# Driver.net
KiCad netlist of a schematic drawn in Altium Designer
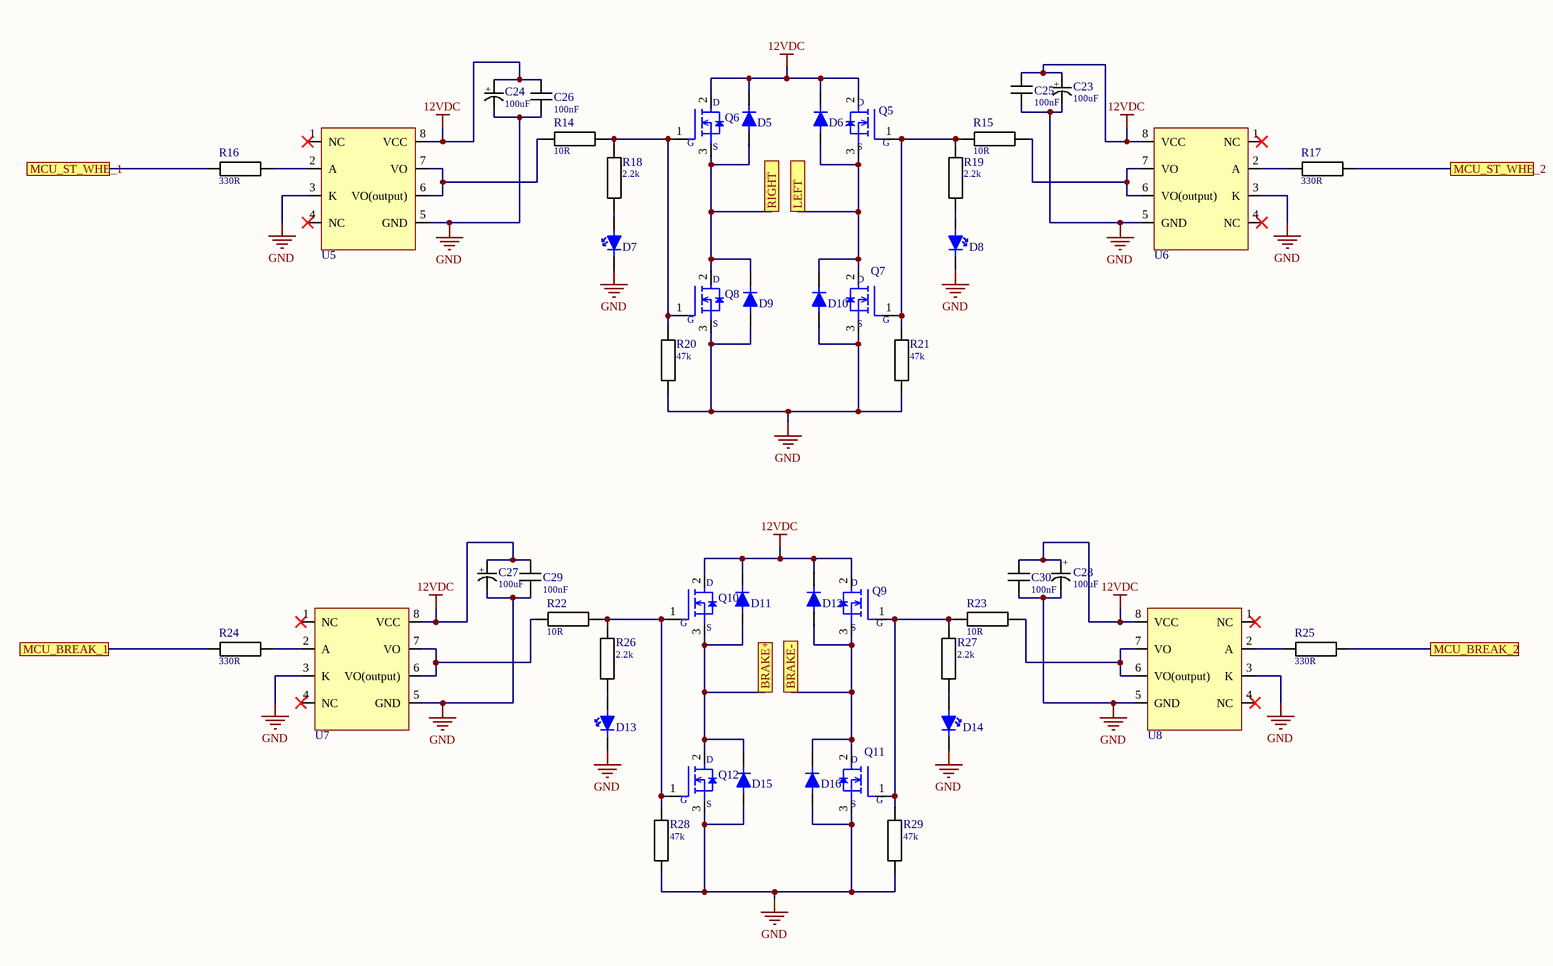
[diagram p0: Driver.SchDoc]

(export (version "E")
  (design (tool "Eeschema 10.0.6"))
  (components
    (comp (ref "C23")
      (value "EEE-HA0J101WR")
      (footprint "CAP_ELEC_EEE-HA0J101WR")
      (description "Cap Aluminum 100uF %20  SMD")
      (fields
        (field (name "MANUFACTURER") "Panasonic")
        (field (name "TOLERANCE") "20%")
        (field (name "CAPACITANCE") "100uF")
        (field (name "DESIGNED BY") "Semih AŞÇI")
      )
      (libsource (lib "Integrated_Library1") (part "CAP 100uF Polar SMD"))
    )
    (comp (ref "C24")
      (value "EEE-HA0J101WR")
      (footprint "CAP_ELEC_EEE-HA0J101WR")
      (description "Cap Aluminum 100uF %20  SMD")
      (fields
        (field (name "MANUFACTURER") "Panasonic")
        (field (name "TOLERANCE") "20%")
        (field (name "CAPACITANCE") "100uF")
        (field (name "DESIGNED BY") "Semih AŞÇI")
      )
      (libsource (lib "Integrated_Library1") (part "CAP 100uF Polar SMD"))
    )
    (comp (ref "C25")
      (value "C0805C104K5RAC7800")
      (footprint "CAP_0805")
      (description "Cap Ceramic 100nF %10 SMD 0805")
      (fields
        (field (name "MANUFACTURER") "KEMET")
        (field (name "MANUFACTURER PART NUMBER") "C0805C104K5RACTU")
        (field (name "CAPACITANCE") "100nF")
        (field (name "DESIGNED BY") "Semih AŞÇI")
      )
      (libsource (lib "Integrated_Library1") (part "CAP 100nF 0805"))
    )
    (comp (ref "C26")
      (value "C0805C104K5RAC7800")
      (footprint "CAP_0805")
      (description "Cap Ceramic 100nF %10 SMD 0805")
      (fields
        (field (name "MANUFACTURER") "KEMET")
        (field (name "MANUFACTURER PART NUMBER") "C0805C104K5RACTU")
        (field (name "CAPACITANCE") "100nF")
        (field (name "DESIGNED BY") "Semih AŞÇI")
      )
      (libsource (lib "Integrated_Library1") (part "CAP 100nF 0805"))
    )
    (comp (ref "C27")
      (value "EEE-HA0J101WR")
      (footprint "CAP_ELEC_EEE-HA0J101WR")
      (description "Cap Aluminum 100uF %20  SMD")
      (fields
        (field (name "MANUFACTURER") "Panasonic")
        (field (name "TOLERANCE") "20%")
        (field (name "CAPACITANCE") "100uF")
        (field (name "DESIGNED BY") "Semih AŞÇI")
      )
      (libsource (lib "Integrated_Library1") (part "CAP 100uF Polar SMD"))
    )
    (comp (ref "C28")
      (value "EEE-HA0J101WR")
      (footprint "CAP_ELEC_EEE-HA0J101WR")
      (description "Cap Aluminum 100uF %20  SMD")
      (fields
        (field (name "MANUFACTURER") "Panasonic")
        (field (name "TOLERANCE") "20%")
        (field (name "CAPACITANCE") "100uF")
        (field (name "DESIGNED BY") "Semih AŞÇI")
      )
      (libsource (lib "") (part "CAP 100uF Polar SMD_1"))
    )
    (comp (ref "C29")
      (value "C0805C104K5RAC7800")
      (footprint "CAP_0805")
      (description "Cap Ceramic 100nF %10 SMD 0805")
      (fields
        (field (name "MANUFACTURER") "KEMET")
        (field (name "MANUFACTURER PART NUMBER") "C0805C104K5RACTU")
        (field (name "CAPACITANCE") "100nF")
        (field (name "DESIGNED BY") "Semih AŞÇI")
      )
      (libsource (lib "Integrated_Library1") (part "CAP 100nF 0805"))
    )
    (comp (ref "C30")
      (value "C0805C104K5RAC7800")
      (footprint "CAP_0805")
      (description "Cap Ceramic 100nF %10 SMD 0805")
      (fields
        (field (name "MANUFACTURER") "KEMET")
        (field (name "MANUFACTURER PART NUMBER") "C0805C104K5RACTU")
        (field (name "CAPACITANCE") "100nF")
        (field (name "DESIGNED BY") "Semih AŞÇI")
      )
      (libsource (lib "Integrated_Library1") (part "CAP 100nF 0805"))
    )
    (comp (ref "D5")
      (value "1N4001W")
      (footprint "SOD-123F")
      (description "Diode Standard Recovery Rectifier 50 Volt 1A 2-Pin SMB Tape and Reel")
      (fields
        (field (name "MANUFACTURER") "Diodes")
        (field (name "MANUFACTURER PART NUMBER") "S1AB-13")
        (field (name "DESIGNED BY") "Semih AŞÇI")
      )
      (libsource (lib "Integrated_Library1") (part "1N4001W"))
    )
    (comp (ref "D6")
      (value "1N4001W")
      (footprint "SOD-123F")
      (description "Diode Standard Recovery Rectifier 50 Volt 1A 2-Pin SMB Tape and Reel")
      (fields
        (field (name "MANUFACTURER") "Diodes")
        (field (name "MANUFACTURER PART NUMBER") "S1AB-13")
        (field (name "DESIGNED BY") "Semih AŞÇI")
      )
      (libsource (lib "Integrated_Library1") (part "1N4001W"))
    )
    (comp (ref "D7")
      (value "LTST-C171GKT")
      (footprint "LED_GREEN_0805")
      (description "Green 0805 130 º Min 5 mcd Typical 12 mcd Water Clear Lens SMT LED")
      (fields (field (name "MANUFACTURER") "Vishay Lite-On") (field (name "DESIGNED BY") "Semih AŞÇI"))
      (libsource (lib "Integrated_Library1") (part "LED GREEN"))
    )
    (comp (ref "D8")
      (value "LTST-C171GKT")
      (footprint "LED_GREEN_0805")
      (description "Green 0805 130 º Min 5 mcd Typical 12 mcd Water Clear Lens SMT LED")
      (fields (field (name "MANUFACTURER") "Vishay Lite-On") (field (name "DESIGNED BY") "Semih AŞÇI"))
      (libsource (lib "Integrated_Library1") (part "LED GREEN"))
    )
    (comp (ref "D9")
      (value "1N4001W")
      (footprint "SOD-123F")
      (description "Diode Standard Recovery Rectifier 50 Volt 1A 2-Pin SMB Tape and Reel")
      (fields
        (field (name "MANUFACTURER") "Diodes")
        (field (name "MANUFACTURER PART NUMBER") "S1AB-13")
        (field (name "DESIGNED BY") "Semih AŞÇI")
      )
      (libsource (lib "Integrated_Library1") (part "1N4001W"))
    )
    (comp (ref "D10")
      (value "1N4001W")
      (footprint "SOD-123F")
      (description "Diode Standard Recovery Rectifier 50 Volt 1A 2-Pin SMB Tape and Reel")
      (fields
        (field (name "MANUFACTURER") "Diodes")
        (field (name "MANUFACTURER PART NUMBER") "S1AB-13")
        (field (name "DESIGNED BY") "Semih AŞÇI")
      )
      (libsource (lib "Integrated_Library1") (part "1N4001W"))
    )
    (comp (ref "D11")
      (value "1N4001W")
      (footprint "SOD-123F")
      (description "Diode Standard Recovery Rectifier 50 Volt 1A 2-Pin SMB Tape and Reel")
      (fields
        (field (name "MANUFACTURER") "Diodes")
        (field (name "MANUFACTURER PART NUMBER") "S1AB-13")
        (field (name "DESIGNED BY") "Semih AŞÇI")
      )
      (libsource (lib "Integrated_Library1") (part "1N4001W"))
    )
    (comp (ref "D12")
      (value "1N4001W")
      (footprint "SOD-123F")
      (description "Diode Standard Recovery Rectifier 50 Volt 1A 2-Pin SMB Tape and Reel")
      (fields
        (field (name "MANUFACTURER") "Diodes")
        (field (name "MANUFACTURER PART NUMBER") "S1AB-13")
        (field (name "DESIGNED BY") "Semih AŞÇI")
      )
      (libsource (lib "Integrated_Library1") (part "1N4001W"))
    )
    (comp (ref "D13")
      (value "LTST-C171GKT")
      (footprint "LED_GREEN_0805")
      (description "Green 0805 130 º Min 5 mcd Typical 12 mcd Water Clear Lens SMT LED")
      (fields (field (name "MANUFACTURER") "Vishay Lite-On") (field (name "DESIGNED BY") "Semih AŞÇI"))
      (libsource (lib "Integrated_Library1") (part "LED GREEN"))
    )
    (comp (ref "D14")
      (value "LTST-C171GKT")
      (footprint "LED_GREEN_0805")
      (description "Green 0805 130 º Min 5 mcd Typical 12 mcd Water Clear Lens SMT LED")
      (fields (field (name "MANUFACTURER") "Vishay Lite-On") (field (name "DESIGNED BY") "Semih AŞÇI"))
      (libsource (lib "Integrated_Library1") (part "LED GREEN"))
    )
    (comp (ref "D15")
      (value "1N4001W")
      (footprint "SOD-123F")
      (description "Diode Standard Recovery Rectifier 50 Volt 1A 2-Pin SMB Tape and Reel")
      (fields
        (field (name "MANUFACTURER") "Diodes")
        (field (name "MANUFACTURER PART NUMBER") "S1AB-13")
        (field (name "DESIGNED BY") "Semih AŞÇI")
      )
      (libsource (lib "Integrated_Library1") (part "1N4001W"))
    )
    (comp (ref "D16")
      (value "1N4001W")
      (footprint "SOD-123F")
      (description "Diode Standard Recovery Rectifier 50 Volt 1A 2-Pin SMB Tape and Reel")
      (fields
        (field (name "MANUFACTURER") "Diodes")
        (field (name "MANUFACTURER PART NUMBER") "S1AB-13")
        (field (name "DESIGNED BY") "Semih AŞÇI")
      )
      (libsource (lib "Integrated_Library1") (part "1N4001W"))
    )
    (comp (ref "Q5")
      (value "IRF4905STRRPBF")
      (footprint "TO-263-3")
      (description "Transistor PNP Mos IRF4905S INTERNATIONAL RECTIFIER RoHS Ampere=64 V=55 D2PAK")
      (fields
        (field (name "MANUFACTURER") "Infineon")
        (field (name "MANUFACTURER PART NUMBER") "IRF4905STRLPBF")
        (field (name "DESIGNED BY") "Semih AŞÇI")
      )
      (libsource (lib "Integrated_Library1") (part "IRF4905STRRPBF"))
    )
    (comp (ref "Q6")
      (value "IRF4905STRRPBF")
      (footprint "TO-263-3")
      (description "Transistor PNP Mos IRF4905S INTERNATIONAL RECTIFIER RoHS Ampere=64 V=55 D2PAK")
      (fields
        (field (name "MANUFACTURER") "Infineon")
        (field (name "MANUFACTURER PART NUMBER") "IRF4905STRLPBF")
        (field (name "DESIGNED BY") "Semih AŞÇI")
      )
      (libsource (lib "Integrated_Library1") (part "IRF4905STRRPBF"))
    )
    (comp (ref "Q7")
      (value "IRF3710STRLPBF")
      (footprint "TO-263-3")
      (description "Single N-Channel 100 V 23 mOhm 130nC HEXFET® Power Mosfet - D2PAK")
      (fields
        (field (name "MANUFACTURER") "International Rectifier")
        (field (name "DESIGNED BY") "Semih AŞÇI")
      )
      (libsource (lib "Integrated_Library1") (part "IRF3710STRLPBF"))
    )
    (comp (ref "Q8")
      (value "IRF3710STRLPBF")
      (footprint "TO-263-3")
      (description "Single N-Channel 100 V 23 mOhm 130nC HEXFET® Power Mosfet - D2PAK")
      (fields
        (field (name "MANUFACTURER") "International Rectifier")
        (field (name "DESIGNED BY") "Semih AŞÇI")
      )
      (libsource (lib "Integrated_Library1") (part "IRF3710STRLPBF"))
    )
    (comp (ref "Q9")
      (value "IRF4905STRRPBF")
      (footprint "TO-263-3")
      (description "Transistor PNP Mos IRF4905S INTERNATIONAL RECTIFIER RoHS Ampere=64 V=55 D2PAK")
      (fields
        (field (name "MANUFACTURER") "Infineon")
        (field (name "MANUFACTURER PART NUMBER") "IRF4905STRLPBF")
        (field (name "DESIGNED BY") "Semih AŞÇI")
      )
      (libsource (lib "Integrated_Library1") (part "IRF4905STRRPBF"))
    )
    (comp (ref "Q10")
      (value "IRF4905STRRPBF")
      (footprint "TO-263-3")
      (description "Transistor PNP Mos IRF4905S INTERNATIONAL RECTIFIER RoHS Ampere=64 V=55 D2PAK")
      (fields
        (field (name "MANUFACTURER") "Infineon")
        (field (name "MANUFACTURER PART NUMBER") "IRF4905STRLPBF")
        (field (name "DESIGNED BY") "Semih AŞÇI")
      )
      (libsource (lib "Integrated_Library1") (part "IRF4905STRRPBF"))
    )
    (comp (ref "Q11")
      (value "IRF3710STRLPBF")
      (footprint "TO-263-3")
      (description "Single N-Channel 100 V 23 mOhm 130nC HEXFET® Power Mosfet - D2PAK")
      (fields
        (field (name "MANUFACTURER") "International Rectifier")
        (field (name "DESIGNED BY") "Semih AŞÇI")
      )
      (libsource (lib "Integrated_Library1") (part "IRF3710STRLPBF"))
    )
    (comp (ref "Q12")
      (value "IRF3710STRLPBF")
      (footprint "TO-263-3")
      (description "Single N-Channel 100 V 23 mOhm 130nC HEXFET® Power Mosfet - D2PAK")
      (fields
        (field (name "MANUFACTURER") "International Rectifier")
        (field (name "DESIGNED BY") "Semih AŞÇI")
      )
      (libsource (lib "Integrated_Library1") (part "IRF3710STRLPBF"))
    )
    (comp (ref "R14")
      (value "RC0805FR-0710RL")
      (footprint "CAP_0805")
      (description "Res 10 Ohm %1 SMD 0805")
      (fields
        (field (name "MANUFACTURER") "Yageo")
        (field (name "TOLERANCE") "1%")
        (field (name "RESISTANCE") "10R")
        (field (name "DESIGNED BY") "Semih AŞÇI")
      )
      (libsource (lib "Integrated_Library1") (part "RES 10 OHM 0805"))
    )
    (comp (ref "R15")
      (value "RC0805FR-0710RL")
      (footprint "CAP_0805")
      (description "Res 10 Ohm %1 SMD 0805")
      (fields
        (field (name "MANUFACTURER") "Yageo")
        (field (name "TOLERANCE") "1%")
        (field (name "RESISTANCE") "10R")
        (field (name "DESIGNED BY") "Semih AŞÇI")
      )
      (libsource (lib "Integrated_Library1") (part "RES 10 OHM 0805"))
    )
    (comp (ref "R16")
      (value "RC0603FR-07330RL")
      (footprint "RES_0603")
      (description "Res 330 Ohm %1 SMD 0603")
      (fields
        (field (name "MANUFACTURER") "Yageo")
        (field (name "TOLERANCE") "1%")
        (field (name "RESISTANCE") "330R")
        (field (name "DESIGNED BY") "Semih AŞÇI")
      )
      (libsource (lib "Integrated_Library1") (part "RES 330 OHM 0603"))
    )
    (comp (ref "R17")
      (value "RC0603FR-07330RL")
      (footprint "RES_0603")
      (description "Res 330 Ohm %1 SMD 0603")
      (fields
        (field (name "MANUFACTURER") "Yageo")
        (field (name "TOLERANCE") "1%")
        (field (name "RESISTANCE") "330R")
        (field (name "DESIGNED BY") "Semih AŞÇI")
      )
      (libsource (lib "Integrated_Library1") (part "RES 330 OHM 0603"))
    )
    (comp (ref "R18")
      (value "RC0603JR-072K2L")
      (footprint "RES_0603")
      (description "Res 2.2k Ohm %5 SMD 0603")
      (fields
        (field (name "MANUFACTURER") "Yageo")
        (field (name "TOLERANCE") "5%")
        (field (name "RESISTANCE") "2.2k")
        (field (name "DESIGNED BY") "Semih AŞÇI")
      )
      (libsource (lib "Integrated_Library1") (part "RES 2.2k OHM 0603"))
    )
    (comp (ref "R19")
      (value "RC0603JR-072K2L")
      (footprint "RES_0603")
      (description "Res 2.2k Ohm %5 SMD 0603")
      (fields
        (field (name "MANUFACTURER") "Yageo")
        (field (name "TOLERANCE") "5%")
        (field (name "RESISTANCE") "2.2k")
        (field (name "DESIGNED BY") "Semih AŞÇI")
      )
      (libsource (lib "Integrated_Library1") (part "RES 2.2k OHM 0603"))
    )
    (comp (ref "R20")
      (value "RC0603JR-0747KL")
      (footprint "RES_0603")
      (description "Res 47k Ohm %5 SMD 0603")
      (fields
        (field (name "MANUFACTURER") "Yageo")
        (field (name "TOLERANCE") "5%")
        (field (name "RESISTANCE") "47k")
        (field (name "DESIGNED BY") "Semih AŞÇI")
      )
      (libsource (lib "Integrated_Library1") (part "RES 47k OHM 0603"))
    )
    (comp (ref "R21")
      (value "RC0603JR-0747KL")
      (footprint "RES_0603")
      (description "Res 47k Ohm %5 SMD 0603")
      (fields
        (field (name "MANUFACTURER") "Yageo")
        (field (name "TOLERANCE") "5%")
        (field (name "RESISTANCE") "47k")
        (field (name "DESIGNED BY") "Semih AŞÇI")
      )
      (libsource (lib "Integrated_Library1") (part "RES 47k OHM 0603"))
    )
    (comp (ref "R22")
      (value "RC0805FR-0710RL")
      (footprint "CAP_0805")
      (description "Res 10 Ohm %1 SMD 0805")
      (fields
        (field (name "MANUFACTURER") "Yageo")
        (field (name "TOLERANCE") "1%")
        (field (name "RESISTANCE") "10R")
        (field (name "DESIGNED BY") "Semih AŞÇI")
      )
      (libsource (lib "Integrated_Library1") (part "RES 10 OHM 0805"))
    )
    (comp (ref "R23")
      (value "RC0805FR-0710RL")
      (footprint "CAP_0805")
      (description "Res 10 Ohm %1 SMD 0805")
      (fields
        (field (name "MANUFACTURER") "Yageo")
        (field (name "TOLERANCE") "1%")
        (field (name "RESISTANCE") "10R")
        (field (name "DESIGNED BY") "Semih AŞÇI")
      )
      (libsource (lib "Integrated_Library1") (part "RES 10 OHM 0805"))
    )
    (comp (ref "R24")
      (value "RC0603FR-07330RL")
      (footprint "RES_0603")
      (description "Res 330 Ohm %1 SMD 0603")
      (fields
        (field (name "MANUFACTURER") "Yageo")
        (field (name "TOLERANCE") "1%")
        (field (name "RESISTANCE") "330R")
        (field (name "DESIGNED BY") "Semih AŞÇI")
      )
      (libsource (lib "Integrated_Library1") (part "RES 330 OHM 0603"))
    )
    (comp (ref "R25")
      (value "RC0603FR-07330RL")
      (footprint "RES_0603")
      (description "Res 330 Ohm %1 SMD 0603")
      (fields
        (field (name "MANUFACTURER") "Yageo")
        (field (name "TOLERANCE") "1%")
        (field (name "RESISTANCE") "330R")
        (field (name "DESIGNED BY") "Semih AŞÇI")
      )
      (libsource (lib "Integrated_Library1") (part "RES 330 OHM 0603"))
    )
    (comp (ref "R26")
      (value "RC0603JR-072K2L")
      (footprint "RES_0603")
      (description "Res 2.2k Ohm %5 SMD 0603")
      (fields
        (field (name "MANUFACTURER") "Yageo")
        (field (name "TOLERANCE") "5%")
        (field (name "RESISTANCE") "2.2k")
        (field (name "DESIGNED BY") "Semih AŞÇI")
      )
      (libsource (lib "Integrated_Library1") (part "RES 2.2k OHM 0603"))
    )
    (comp (ref "R27")
      (value "RC0603JR-072K2L")
      (footprint "RES_0603")
      (description "Res 2.2k Ohm %5 SMD 0603")
      (fields
        (field (name "MANUFACTURER") "Yageo")
        (field (name "TOLERANCE") "5%")
        (field (name "RESISTANCE") "2.2k")
        (field (name "DESIGNED BY") "Semih AŞÇI")
      )
      (libsource (lib "Integrated_Library1") (part "RES 2.2k OHM 0603"))
    )
    (comp (ref "R28")
      (value "RC0603JR-0747KL")
      (footprint "RES_0603")
      (description "Res 47k Ohm %5 SMD 0603")
      (fields
        (field (name "MANUFACTURER") "Yageo")
        (field (name "TOLERANCE") "5%")
        (field (name "RESISTANCE") "47k")
        (field (name "DESIGNED BY") "Semih AŞÇI")
      )
      (libsource (lib "Integrated_Library1") (part "RES 47k OHM 0603"))
    )
    (comp (ref "R29")
      (value "RC0603JR-0747KL")
      (footprint "RES_0603")
      (description "Res 47k Ohm %5 SMD 0603")
      (fields
        (field (name "MANUFACTURER") "Yageo")
        (field (name "TOLERANCE") "5%")
        (field (name "RESISTANCE") "47k")
        (field (name "DESIGNED BY") "Semih AŞÇI")
      )
      (libsource (lib "Integrated_Library1") (part "RES 47k OHM 0603"))
    )
    (comp (ref "U5")
      (value "TLP250LF1F")
      (footprint "8-SMD")
      (description "Photocoupler Hs Trans Out 8-SMD")
      (fields
        (field (name "MANUFACTURER") "Toshiba")
        (field (name "MANUFACTURER PART NUMBER") "TLP250(LF1,F)")
        (field (name "DESIGNED BY") "Semih AŞÇI")
      )
      (libsource (lib "") (part "TLP250_1"))
    )
    (comp (ref "U6")
      (value "TLP250LF1F")
      (footprint "8-SMD")
      (description "Photocoupler Hs Trans Out 8-SMD")
      (fields
        (field (name "MANUFACTURER") "Toshiba")
        (field (name "MANUFACTURER PART NUMBER") "TLP250(LF1,F)")
        (field (name "DESIGNED BY") "Semih AŞÇI")
      )
      (libsource (lib "Integrated_Library1") (part "TLP250"))
    )
    (comp (ref "U7")
      (value "TLP250LF1F")
      (footprint "8-SMD")
      (description "Photocoupler Hs Trans Out 8-SMD")
      (fields
        (field (name "MANUFACTURER") "Toshiba")
        (field (name "MANUFACTURER PART NUMBER") "TLP250(LF1,F)")
        (field (name "DESIGNED BY") "Semih AŞÇI")
      )
      (libsource (lib "") (part "TLP250_1"))
    )
    (comp (ref "U8")
      (value "TLP250LF1F")
      (footprint "8-SMD")
      (description "Photocoupler Hs Trans Out 8-SMD")
      (fields
        (field (name "MANUFACTURER") "Toshiba")
        (field (name "MANUFACTURER PART NUMBER") "TLP250(LF1,F)")
        (field (name "DESIGNED BY") "Semih AŞÇI")
      )
      (libsource (lib "Integrated_Library1") (part "TLP250"))
    )
  )
  (nets
    (net (code "1") (name "/BRAKE+") (class "Default")
      (node (ref "D11") (pin "2") (pinfunction "2_2") (pintype "passive"))
      (node (ref "D15") (pin "1") (pinfunction "1_1") (pintype "passive"))
      (node (ref "Q10") (pin "3") (pinfunction "D_3") (pintype "passive"))
      (node (ref "Q12") (pin "2") (pinfunction "G_2") (pintype "passive"))
    )
    (net (code "2") (name "/BRAKE-") (class "Default")
      (node (ref "D12") (pin "2") (pinfunction "2_2") (pintype "passive"))
      (node (ref "D16") (pin "1") (pinfunction "1_1") (pintype "passive"))
      (node (ref "Q11") (pin "2") (pinfunction "G_2") (pintype "passive"))
      (node (ref "Q9") (pin "3") (pinfunction "D_3") (pintype "passive"))
    )
    (net (code "3") (name "/LEFT") (class "Default")
      (node (ref "D10") (pin "1") (pinfunction "1_1") (pintype "passive"))
      (node (ref "D6") (pin "2") (pinfunction "2_2") (pintype "passive"))
      (node (ref "Q5") (pin "3") (pinfunction "D_3") (pintype "passive"))
      (node (ref "Q7") (pin "2") (pinfunction "G_2") (pintype "passive"))
    )
    (net (code "4") (name "/MCU_BREAK_1") (class "Default")
      (node (ref "R24") (pin "1") (pinfunction "1_1") (pintype "passive"))
    )
    (net (code "5") (name "/MCU_BREAK_2") (class "Default")
      (node (ref "R25") (pin "1") (pinfunction "1_1") (pintype "passive"))
    )
    (net (code "6") (name "/MCU_ST_WHE_1") (class "Default")
      (node (ref "R16") (pin "1") (pinfunction "1_1") (pintype "passive"))
    )
    (net (code "7") (name "/MCU_ST_WHE_2") (class "Default")
      (node (ref "R17") (pin "1") (pinfunction "1_1") (pintype "passive"))
    )
    (net (code "8") (name "/RIGHT") (class "Default")
      (node (ref "D5") (pin "2") (pinfunction "2_2") (pintype "passive"))
      (node (ref "D9") (pin "1") (pinfunction "1_1") (pintype "passive"))
      (node (ref "Q6") (pin "3") (pinfunction "D_3") (pintype "passive"))
      (node (ref "Q8") (pin "2") (pinfunction "G_2") (pintype "passive"))
    )
    (net (code "9") (name "12VDC") (class "Default")
      (node (ref "C23") (pin "1") (pinfunction "1_1") (pintype "passive"))
      (node (ref "C24") (pin "1") (pinfunction "1_1") (pintype "passive"))
      (node (ref "C25") (pin "2") (pinfunction "2_2") (pintype "passive"))
      (node (ref "C26") (pin "2") (pinfunction "2_2") (pintype "passive"))
      (node (ref "C27") (pin "1") (pinfunction "1_1") (pintype "passive"))
      (node (ref "C28") (pin "1") (pinfunction "1_1") (pintype "passive"))
      (node (ref "C29") (pin "2") (pinfunction "2_2") (pintype "passive"))
      (node (ref "C30") (pin "2") (pinfunction "2_2") (pintype "passive"))
      (node (ref "D11") (pin "1") (pinfunction "1_1") (pintype "passive"))
      (node (ref "D12") (pin "1") (pinfunction "1_1") (pintype "passive"))
      (node (ref "D5") (pin "1") (pinfunction "1_1") (pintype "passive"))
      (node (ref "D6") (pin "1") (pinfunction "1_1") (pintype "passive"))
      (node (ref "Q10") (pin "2") (pinfunction "G_2") (pintype "passive"))
      (node (ref "Q5") (pin "2") (pinfunction "G_2") (pintype "passive"))
      (node (ref "Q6") (pin "2") (pinfunction "G_2") (pintype "passive"))
      (node (ref "Q9") (pin "2") (pinfunction "G_2") (pintype "passive"))
      (node (ref "U5") (pin "8") (pinfunction "VCC_8") (pintype "passive"))
      (node (ref "U6") (pin "8") (pinfunction "VCC_8") (pintype "passive"))
      (node (ref "U7") (pin "8") (pinfunction "VCC_8") (pintype "passive"))
      (node (ref "U8") (pin "8") (pinfunction "VCC_8") (pintype "passive"))
    )
    (net (code "10") (name "GND") (class "Default")
      (node (ref "C23") (pin "2") (pinfunction "2_2") (pintype "passive"))
      (node (ref "C24") (pin "2") (pinfunction "2_2") (pintype "passive"))
      (node (ref "C25") (pin "1") (pinfunction "1_1") (pintype "passive"))
      (node (ref "C26") (pin "1") (pinfunction "1_1") (pintype "passive"))
      (node (ref "C27") (pin "2") (pinfunction "2_2") (pintype "passive"))
      (node (ref "C28") (pin "2") (pinfunction "2_2") (pintype "passive"))
      (node (ref "C29") (pin "1") (pinfunction "1_1") (pintype "passive"))
      (node (ref "C30") (pin "1") (pinfunction "1_1") (pintype "passive"))
      (node (ref "D10") (pin "2") (pinfunction "2_2") (pintype "passive"))
      (node (ref "D13") (pin "1") (pinfunction "1_1") (pintype "passive"))
      (node (ref "D14") (pin "1") (pinfunction "1_1") (pintype "passive"))
      (node (ref "D15") (pin "2") (pinfunction "2_2") (pintype "passive"))
      (node (ref "D16") (pin "2") (pinfunction "2_2") (pintype "passive"))
      (node (ref "D7") (pin "1") (pinfunction "1_1") (pintype "passive"))
      (node (ref "D8") (pin "1") (pinfunction "1_1") (pintype "passive"))
      (node (ref "D9") (pin "2") (pinfunction "2_2") (pintype "passive"))
      (node (ref "Q11") (pin "3") (pinfunction "D_3") (pintype "passive"))
      (node (ref "Q12") (pin "3") (pinfunction "D_3") (pintype "passive"))
      (node (ref "Q7") (pin "3") (pinfunction "D_3") (pintype "passive"))
      (node (ref "Q8") (pin "3") (pinfunction "D_3") (pintype "passive"))
      (node (ref "R20") (pin "1") (pinfunction "1_1") (pintype "passive"))
      (node (ref "R21") (pin "1") (pinfunction "1_1") (pintype "passive"))
      (node (ref "R28") (pin "1") (pinfunction "1_1") (pintype "passive"))
      (node (ref "R29") (pin "1") (pinfunction "1_1") (pintype "passive"))
      (node (ref "U5") (pin "3") (pinfunction "K_3") (pintype "passive"))
      (node (ref "U5") (pin "5") (pinfunction "GND_5") (pintype "passive"))
      (node (ref "U6") (pin "3") (pinfunction "K_3") (pintype "passive"))
      (node (ref "U6") (pin "5") (pinfunction "GND_5") (pintype "passive"))
      (node (ref "U7") (pin "3") (pinfunction "K_3") (pintype "passive"))
      (node (ref "U7") (pin "5") (pinfunction "GND_5") (pintype "passive"))
      (node (ref "U8") (pin "3") (pinfunction "K_3") (pintype "passive"))
      (node (ref "U8") (pin "5") (pinfunction "GND_5") (pintype "passive"))
    )
    (net (code "11") (name "Net-(D7-Pad2)") (class "Default")
      (node (ref "D7") (pin "2") (pinfunction "2_2") (pintype "passive"))
      (node (ref "R18") (pin "1") (pinfunction "1_1") (pintype "passive"))
    )
    (net (code "12") (name "Net-(D8-Pad2)") (class "Default")
      (node (ref "D8") (pin "2") (pinfunction "2_2") (pintype "passive"))
      (node (ref "R19") (pin "1") (pinfunction "1_1") (pintype "passive"))
    )
    (net (code "13") (name "Net-(D13-Pad2)") (class "Default")
      (node (ref "D13") (pin "2") (pinfunction "2_2") (pintype "passive"))
      (node (ref "R26") (pin "1") (pinfunction "1_1") (pintype "passive"))
    )
    (net (code "14") (name "Net-(D14-Pad2)") (class "Default")
      (node (ref "D14") (pin "2") (pinfunction "2_2") (pintype "passive"))
      (node (ref "R27") (pin "1") (pinfunction "1_1") (pintype "passive"))
    )
    (net (code "15") (name "Net-(Q5-S)") (class "Default")
      (node (ref "Q5") (pin "1") (pinfunction "S_1") (pintype "passive"))
      (node (ref "Q7") (pin "1") (pinfunction "S_1") (pintype "passive"))
      (node (ref "R15") (pin "2") (pinfunction "2_2") (pintype "passive"))
      (node (ref "R19") (pin "2") (pinfunction "2_2") (pintype "passive"))
      (node (ref "R21") (pin "2") (pinfunction "2_2") (pintype "passive"))
    )
    (net (code "16") (name "Net-(Q6-S)") (class "Default")
      (node (ref "Q6") (pin "1") (pinfunction "S_1") (pintype "passive"))
      (node (ref "Q8") (pin "1") (pinfunction "S_1") (pintype "passive"))
      (node (ref "R14") (pin "2") (pinfunction "2_2") (pintype "passive"))
      (node (ref "R18") (pin "2") (pinfunction "2_2") (pintype "passive"))
      (node (ref "R20") (pin "2") (pinfunction "2_2") (pintype "passive"))
    )
    (net (code "17") (name "Net-(Q10-S)") (class "Default")
      (node (ref "Q10") (pin "1") (pinfunction "S_1") (pintype "passive"))
      (node (ref "Q12") (pin "1") (pinfunction "S_1") (pintype "passive"))
      (node (ref "R22") (pin "2") (pinfunction "2_2") (pintype "passive"))
      (node (ref "R26") (pin "2") (pinfunction "2_2") (pintype "passive"))
      (node (ref "R28") (pin "2") (pinfunction "2_2") (pintype "passive"))
    )
    (net (code "18") (name "Net-(Q11-S)") (class "Default")
      (node (ref "Q11") (pin "1") (pinfunction "S_1") (pintype "passive"))
      (node (ref "Q9") (pin "1") (pinfunction "S_1") (pintype "passive"))
      (node (ref "R23") (pin "2") (pinfunction "2_2") (pintype "passive"))
      (node (ref "R27") (pin "2") (pinfunction "2_2") (pintype "passive"))
      (node (ref "R29") (pin "2") (pinfunction "2_2") (pintype "passive"))
    )
    (net (code "19") (name "Net-(U5-A)") (class "Default")
      (node (ref "R16") (pin "2") (pinfunction "2_2") (pintype "passive"))
      (node (ref "U5") (pin "2") (pinfunction "A_2") (pintype "passive"))
    )
    (net (code "20") (name "Net-(U5-VO(output))") (class "Default")
      (node (ref "R14") (pin "1") (pinfunction "1_1") (pintype "passive"))
      (node (ref "U5") (pin "6") (pinfunction "VO(output)_6") (pintype "passive"))
      (node (ref "U5") (pin "7") (pinfunction "VO_7") (pintype "passive"))
    )
    (net (code "21") (name "Net-(U6-A)") (class "Default")
      (node (ref "R17") (pin "2") (pinfunction "2_2") (pintype "passive"))
      (node (ref "U6") (pin "2") (pinfunction "A_2") (pintype "passive"))
    )
    (net (code "22") (name "Net-(U6-VO(output))") (class "Default")
      (node (ref "R15") (pin "1") (pinfunction "1_1") (pintype "passive"))
      (node (ref "U6") (pin "6") (pinfunction "VO(output)_6") (pintype "passive"))
      (node (ref "U6") (pin "7") (pinfunction "VO_7") (pintype "passive"))
    )
    (net (code "23") (name "Net-(U7-A)") (class "Default")
      (node (ref "R24") (pin "2") (pinfunction "2_2") (pintype "passive"))
      (node (ref "U7") (pin "2") (pinfunction "A_2") (pintype "passive"))
    )
    (net (code "24") (name "Net-(U7-VO(output))") (class "Default")
      (node (ref "R22") (pin "1") (pinfunction "1_1") (pintype "passive"))
      (node (ref "U7") (pin "6") (pinfunction "VO(output)_6") (pintype "passive"))
      (node (ref "U7") (pin "7") (pinfunction "VO_7") (pintype "passive"))
    )
    (net (code "25") (name "Net-(U8-A)") (class "Default")
      (node (ref "R25") (pin "2") (pinfunction "2_2") (pintype "passive"))
      (node (ref "U8") (pin "2") (pinfunction "A_2") (pintype "passive"))
    )
    (net (code "26") (name "Net-(U8-VO(output))") (class "Default")
      (node (ref "R23") (pin "1") (pinfunction "1_1") (pintype "passive"))
      (node (ref "U8") (pin "6") (pinfunction "VO(output)_6") (pintype "passive"))
      (node (ref "U8") (pin "7") (pinfunction "VO_7") (pintype "passive"))
    )
    (net (code "27") (name "unconnected-(U5-NC-Pad1)") (class "Default")
      (node (ref "U5") (pin "1") (pinfunction "NC_1") (pintype "passive+no_connect"))
    )
    (net (code "28") (name "unconnected-(U5-NC-Pad4)") (class "Default")
      (node (ref "U5") (pin "4") (pinfunction "NC_4") (pintype "passive+no_connect"))
    )
    (net (code "29") (name "unconnected-(U6-NC-Pad1)") (class "Default")
      (node (ref "U6") (pin "1") (pinfunction "NC_1") (pintype "passive+no_connect"))
    )
    (net (code "30") (name "unconnected-(U6-NC-Pad4)") (class "Default")
      (node (ref "U6") (pin "4") (pinfunction "NC_4") (pintype "passive+no_connect"))
    )
    (net (code "31") (name "unconnected-(U7-NC-Pad1)") (class "Default")
      (node (ref "U7") (pin "1") (pinfunction "NC_1") (pintype "passive+no_connect"))
    )
    (net (code "32") (name "unconnected-(U7-NC-Pad4)") (class "Default")
      (node (ref "U7") (pin "4") (pinfunction "NC_4") (pintype "passive+no_connect"))
    )
    (net (code "33") (name "unconnected-(U8-NC-Pad1)") (class "Default")
      (node (ref "U8") (pin "1") (pinfunction "NC_1") (pintype "passive+no_connect"))
    )
    (net (code "34") (name "unconnected-(U8-NC-Pad4)") (class "Default")
      (node (ref "U8") (pin "4") (pinfunction "NC_4") (pintype "passive+no_connect"))
    )
  )
)
